# 3_Communication.net
KiCad netlist of a schematic drawn in Altium Designer
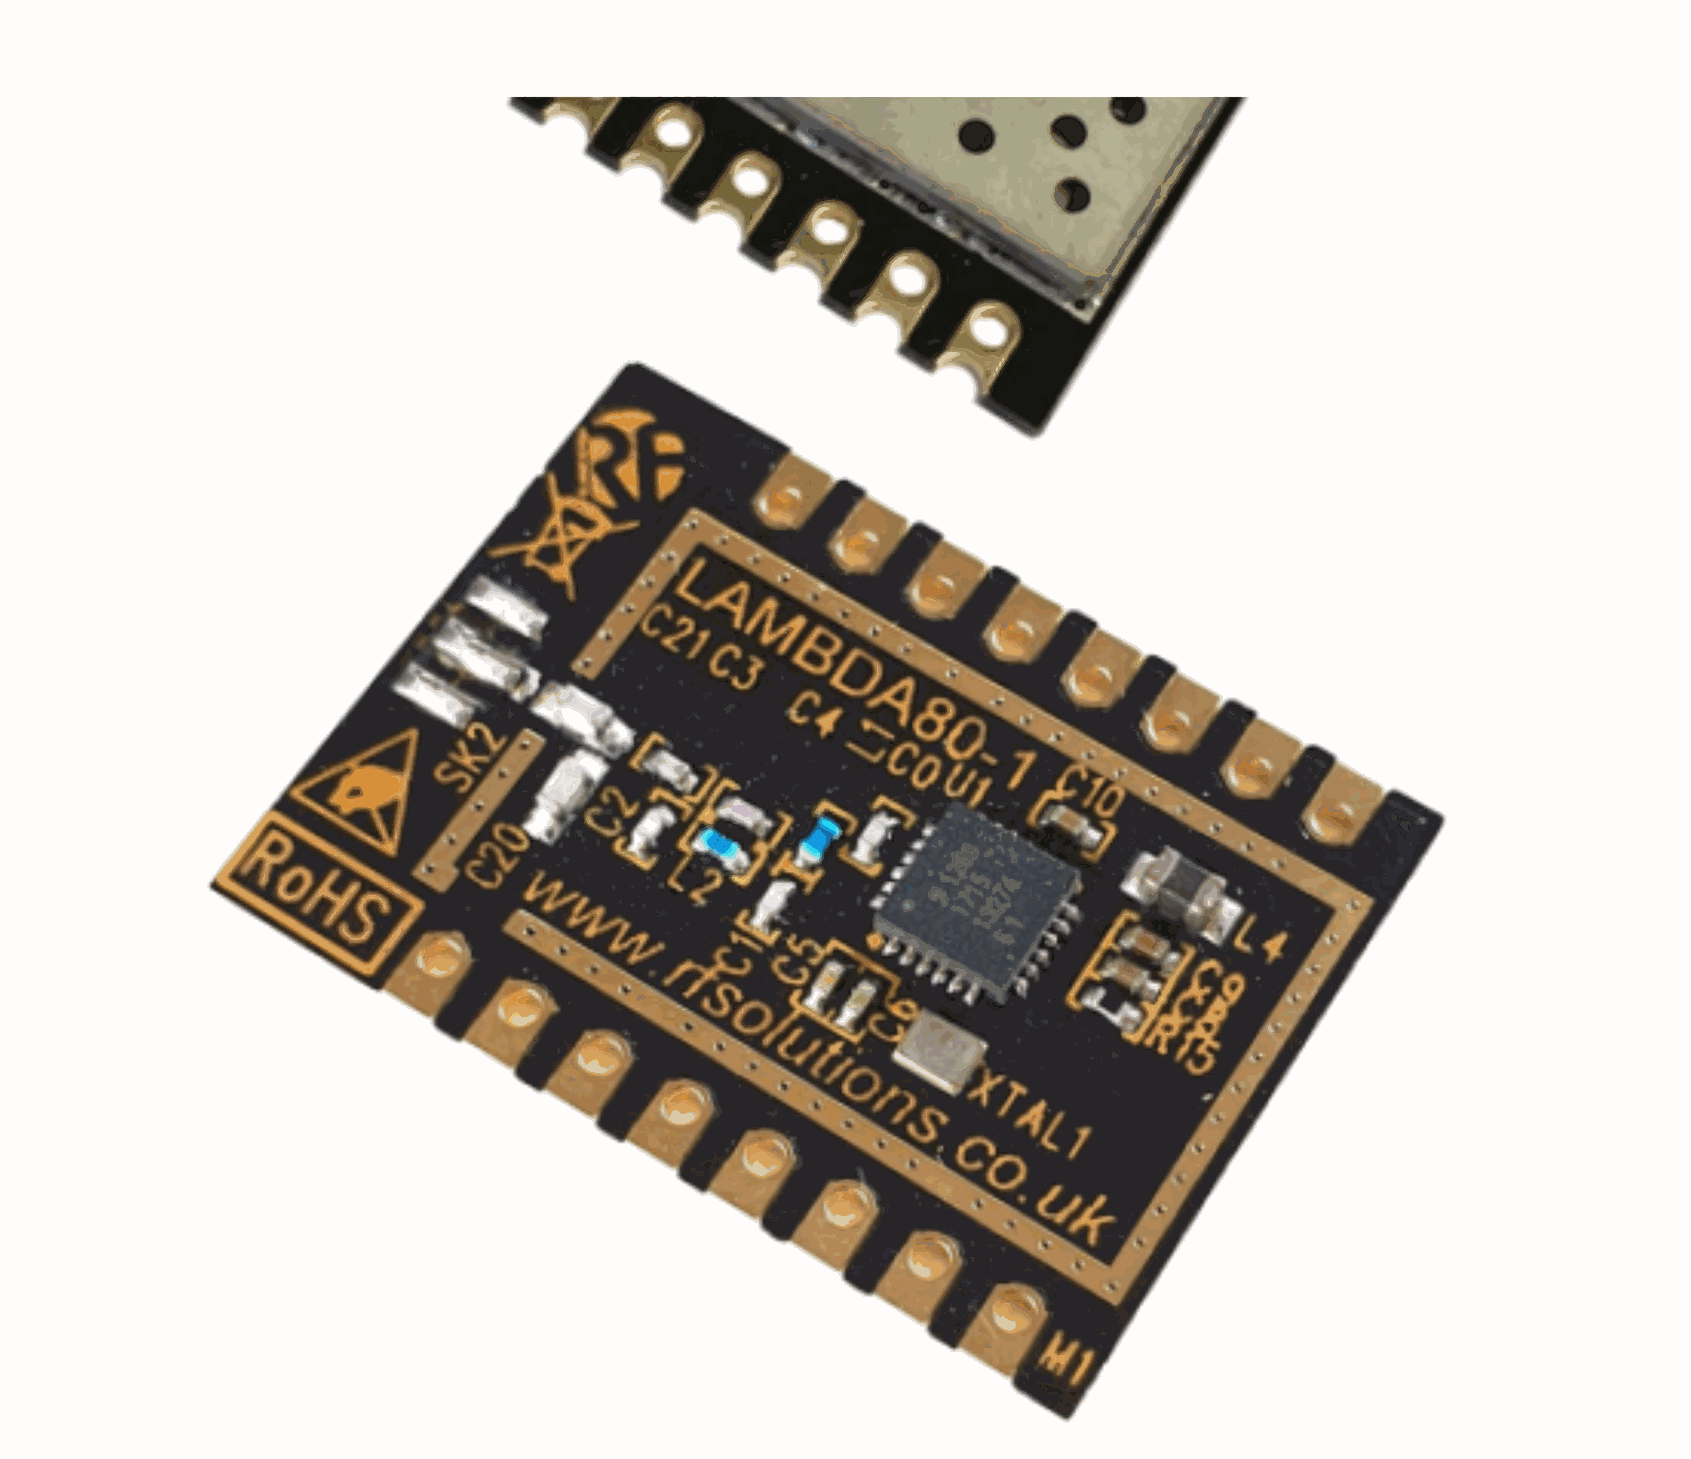
[diagram p0: 3_Communication.SchDoc, top middle]
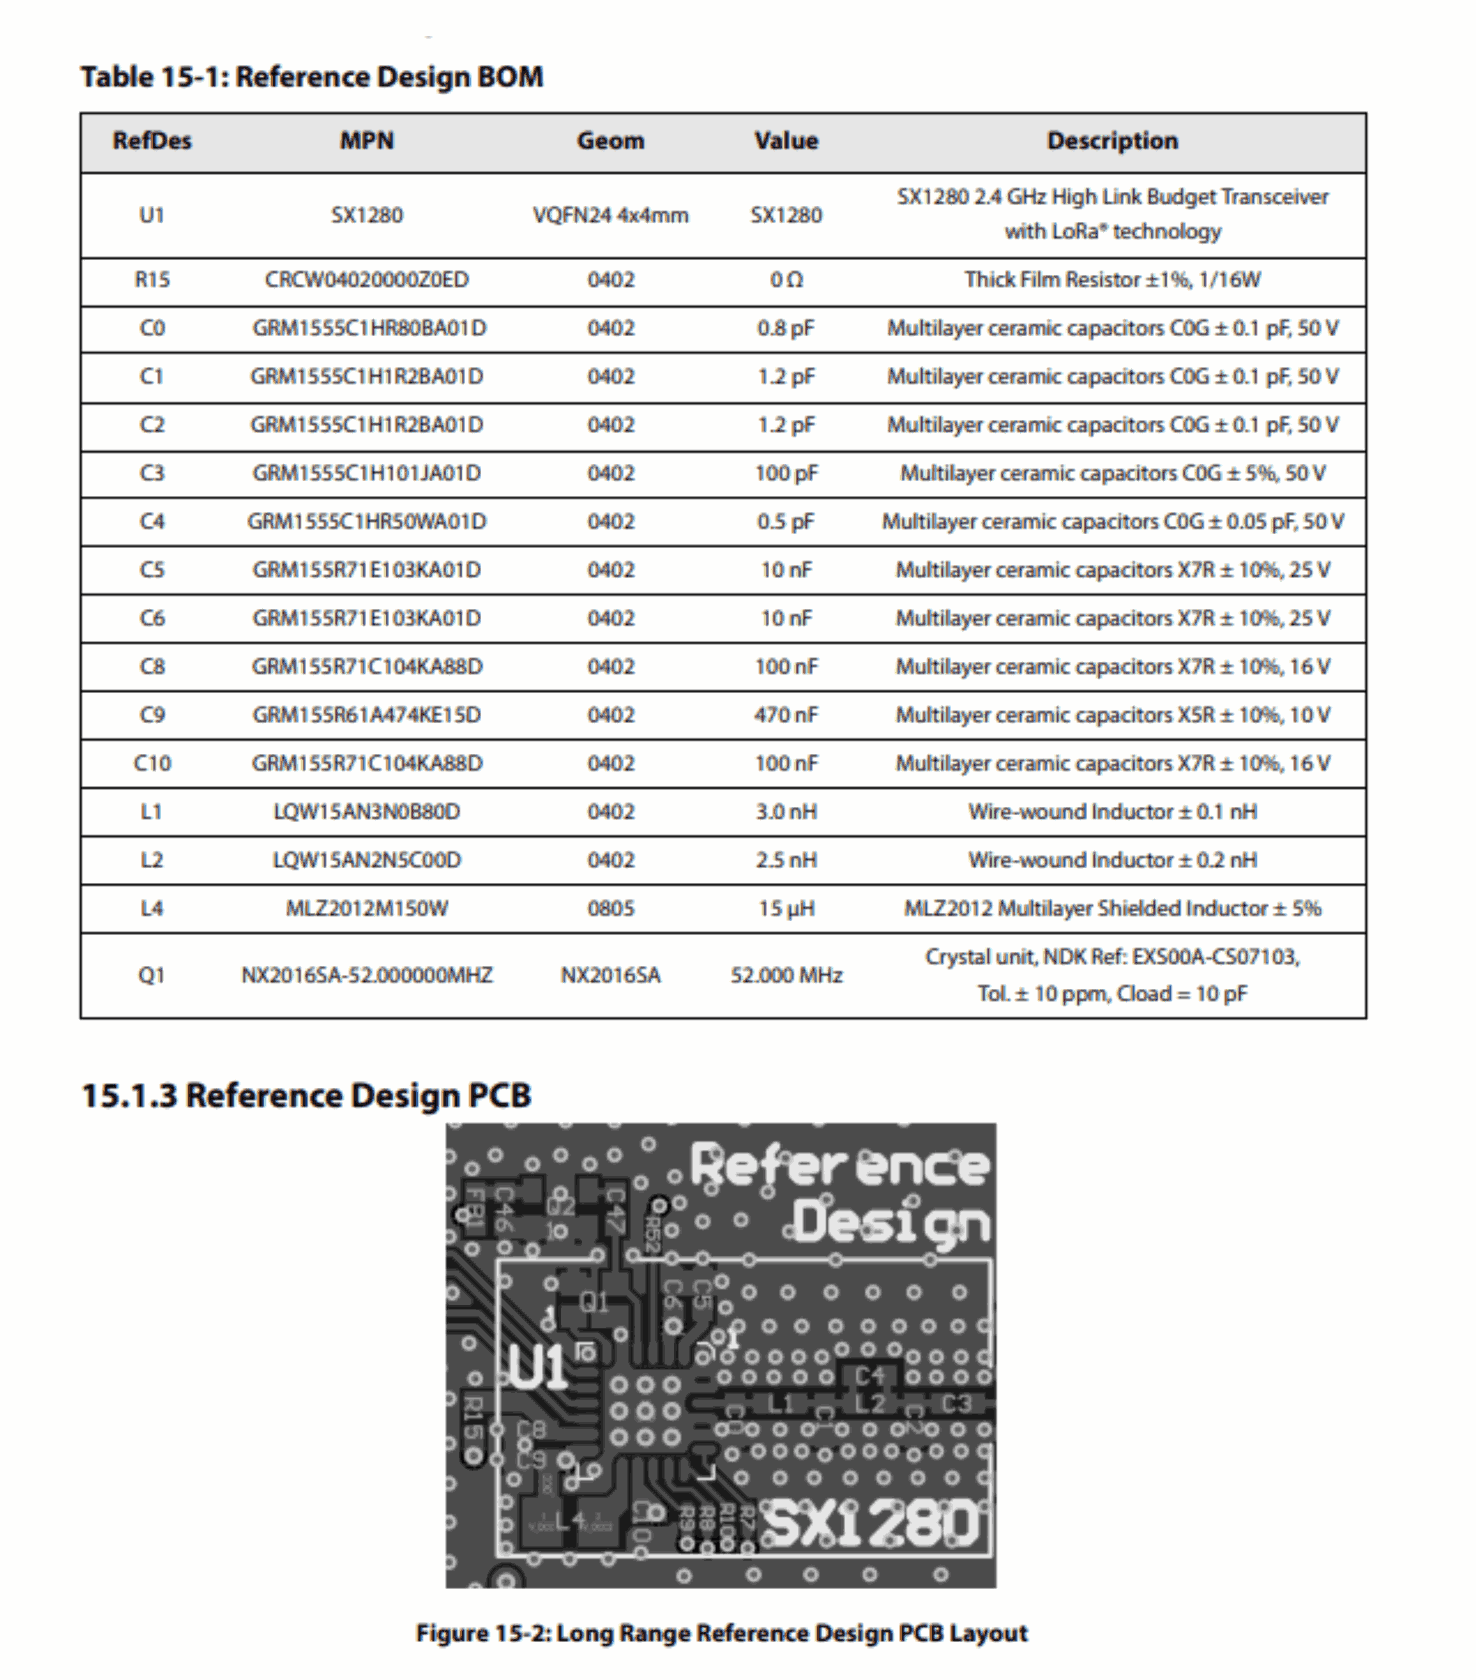
[diagram p1: 3_Communication.SchDoc, top right]
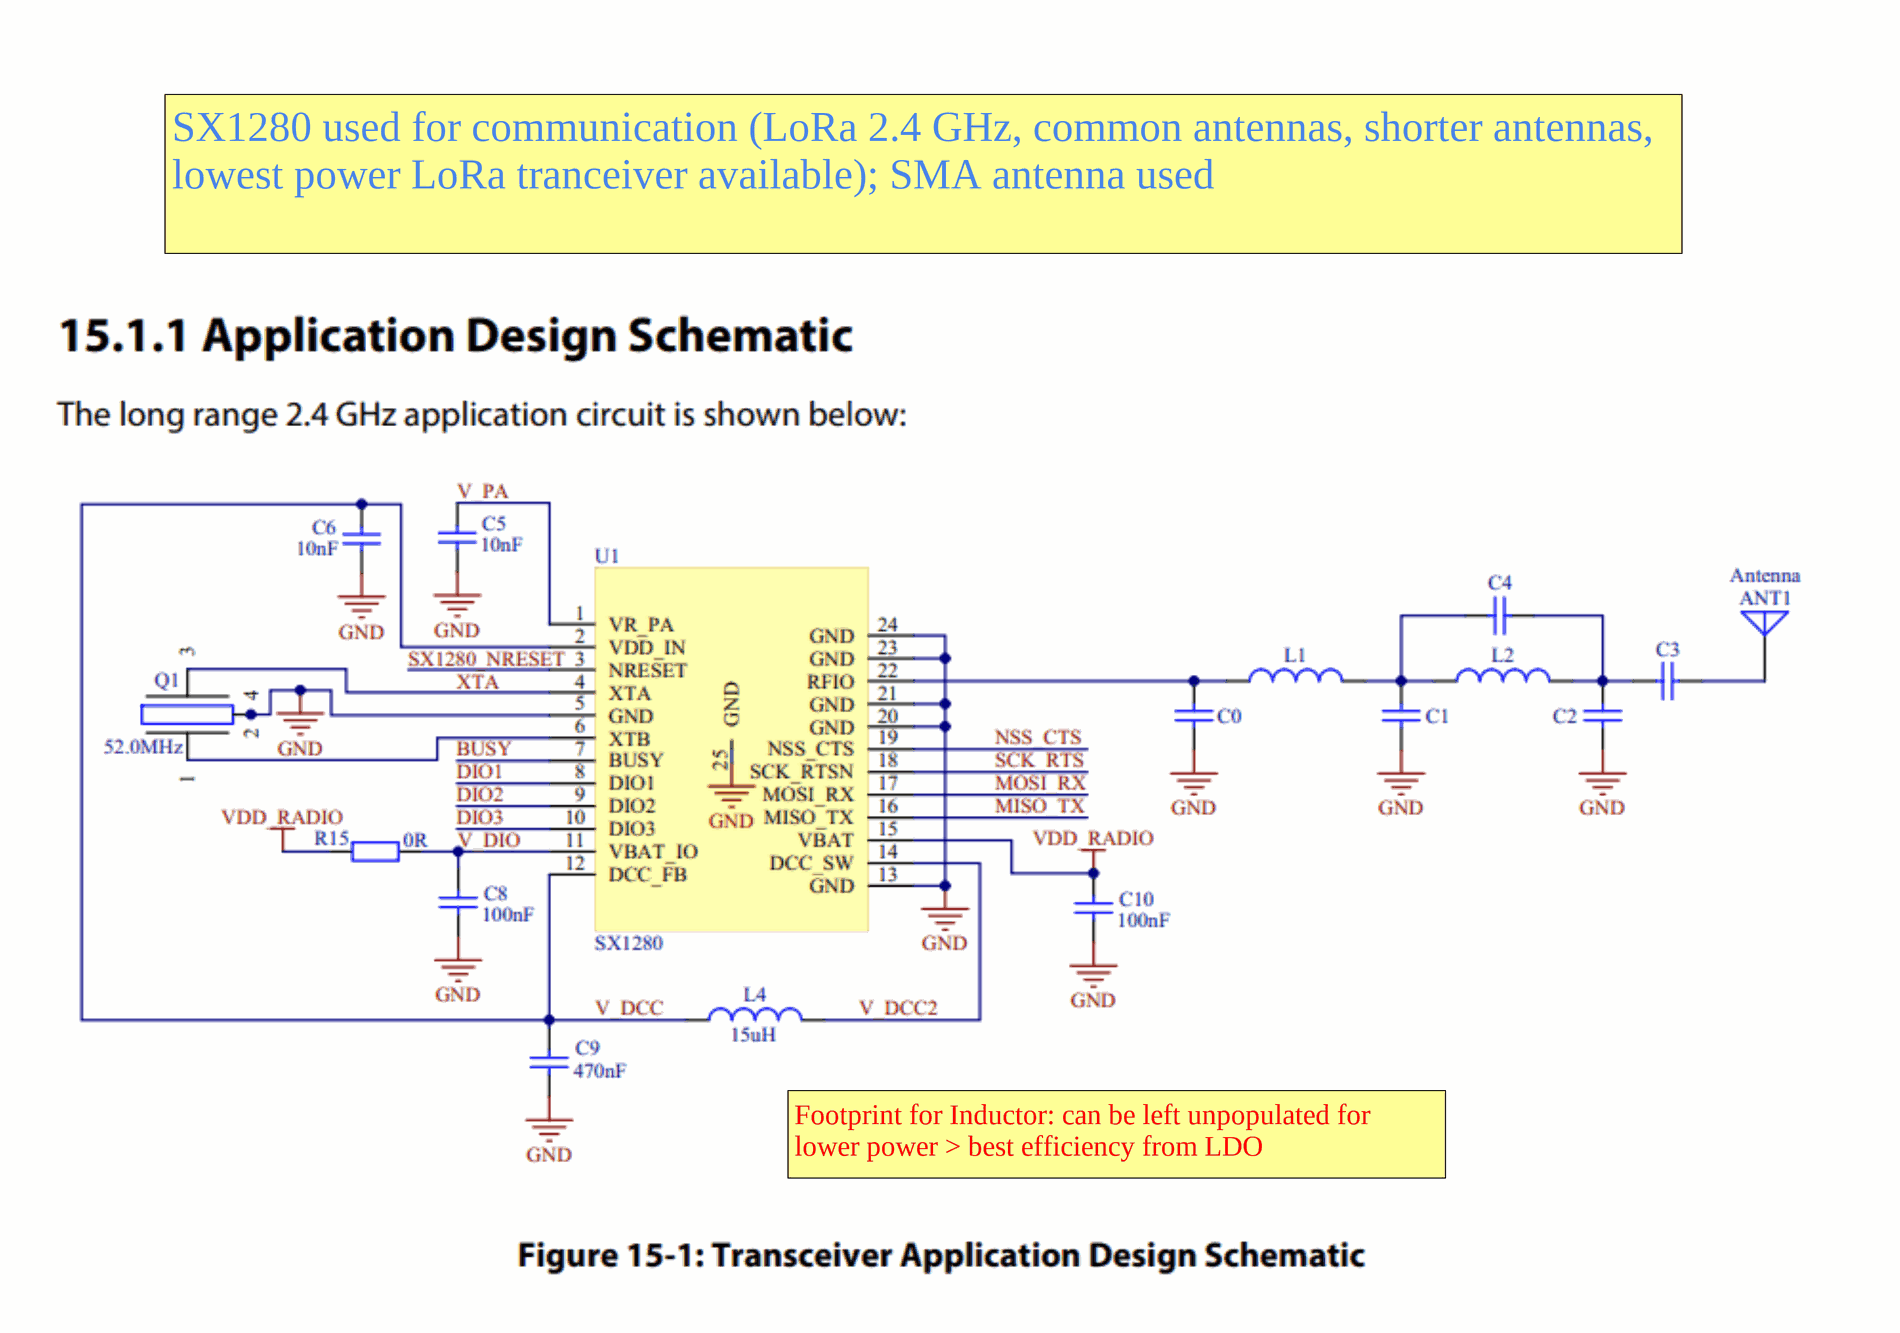
[diagram p2: 3_Communication.SchDoc, bottom left]
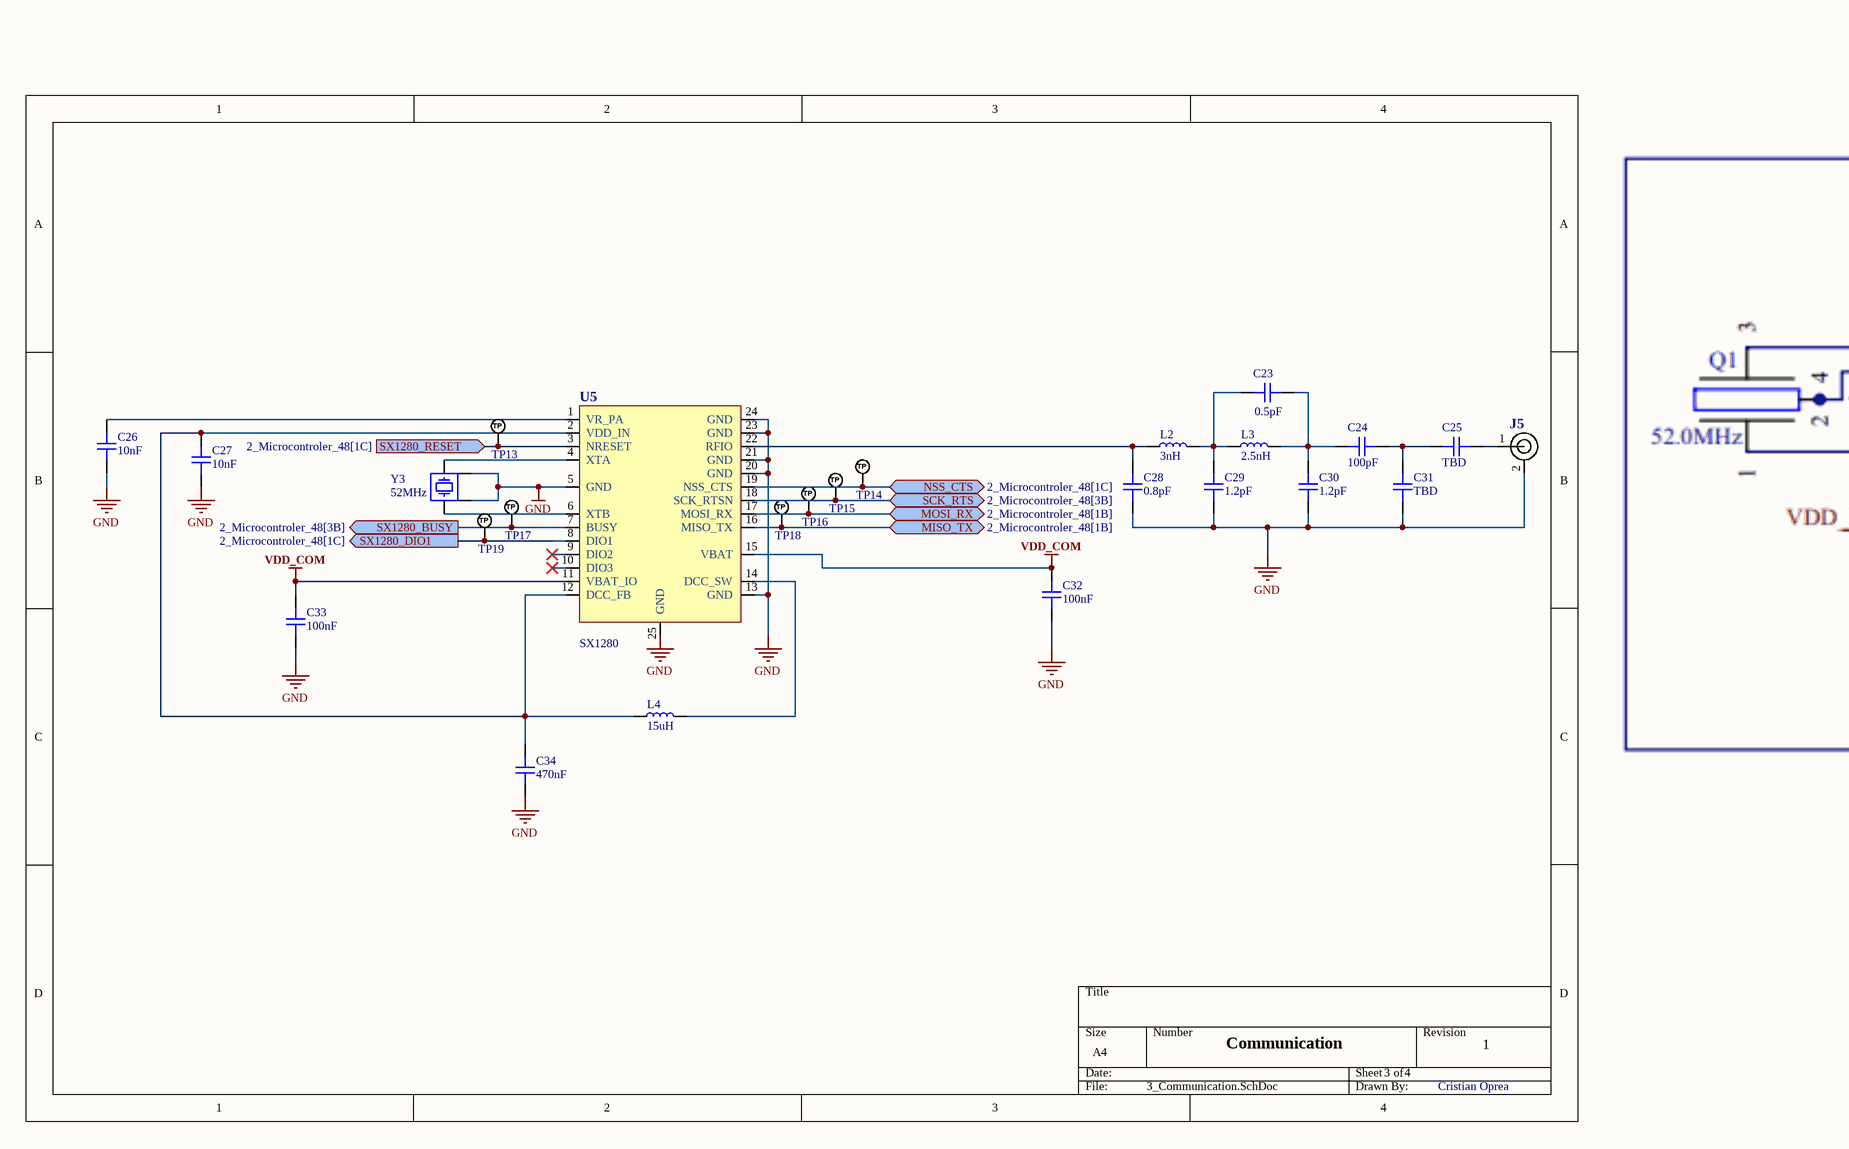
[diagram p3: 3_Communication.SchDoc, bottom middle]
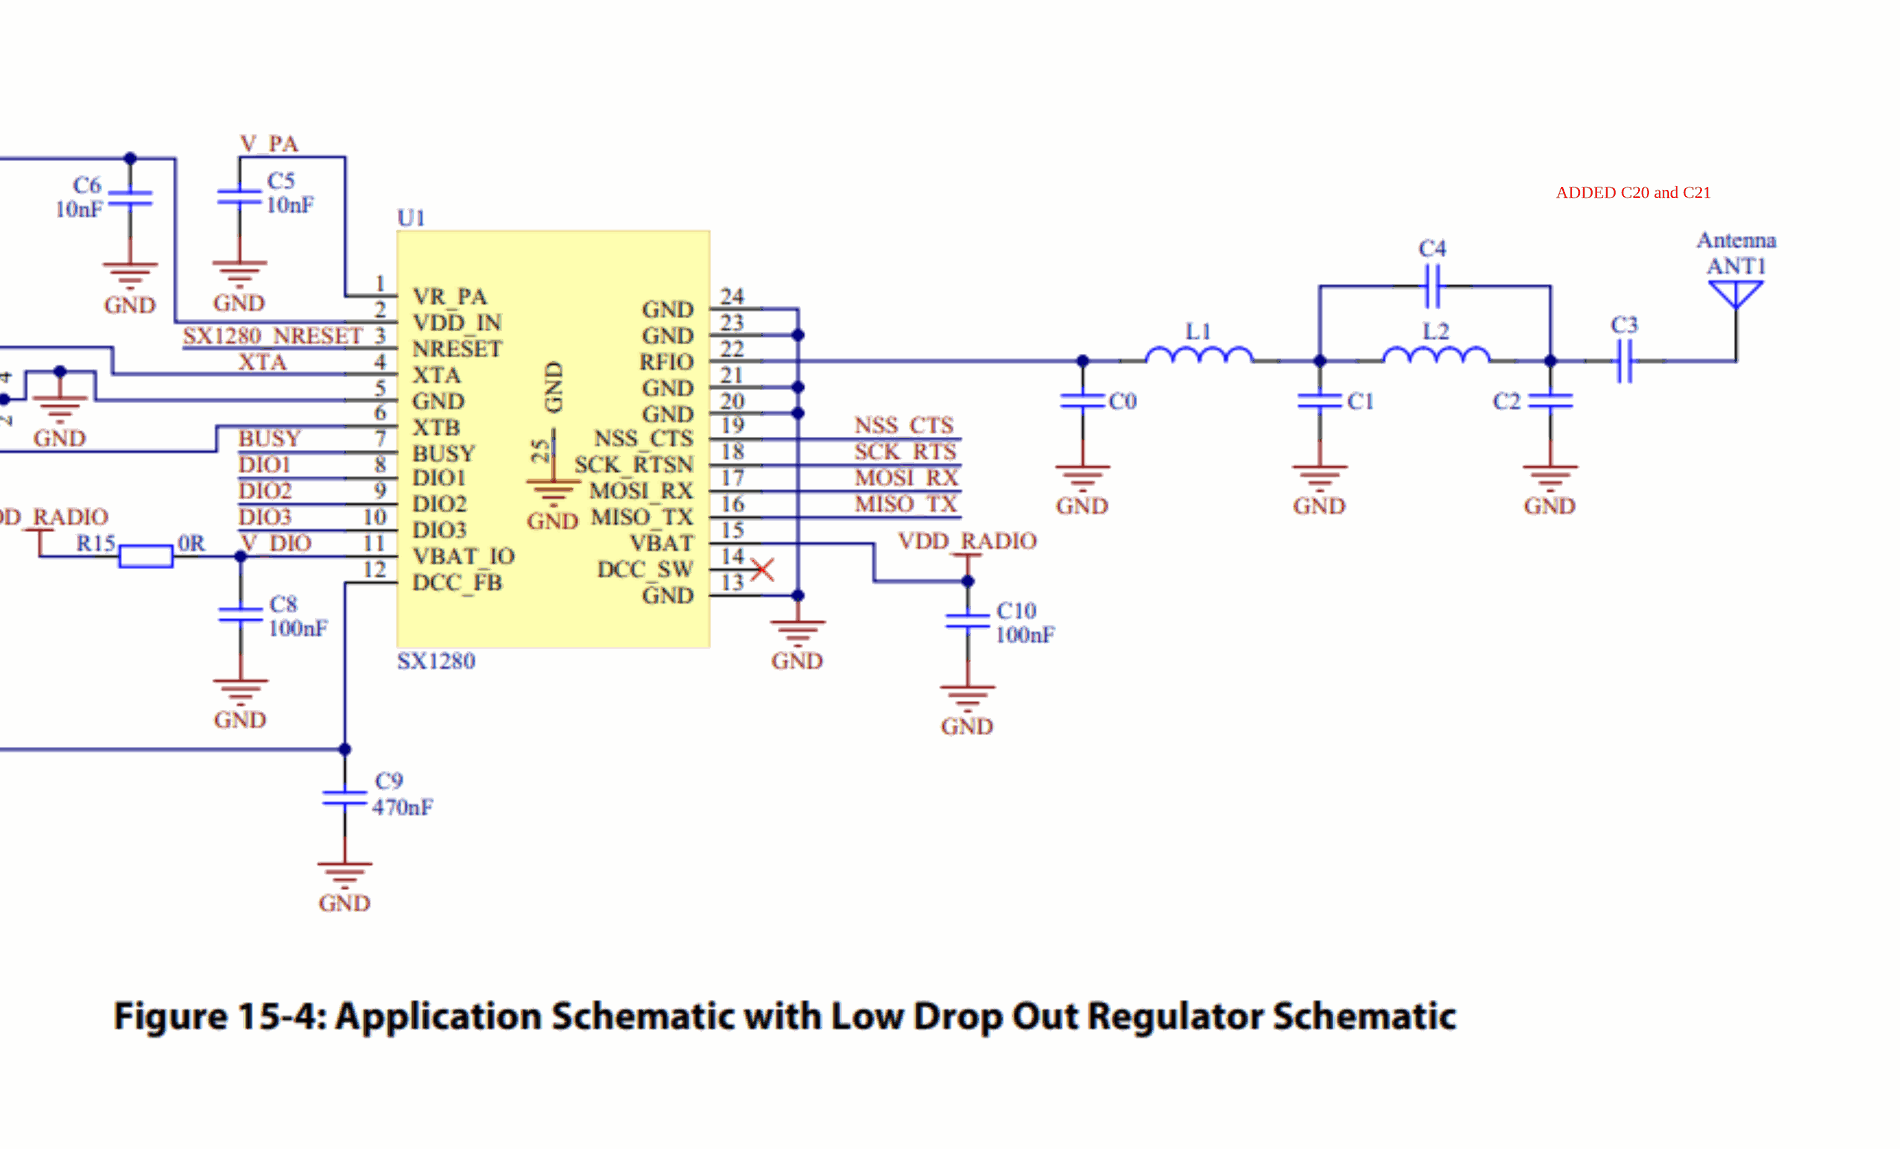
[diagram p4: 3_Communication.SchDoc, bottom right]

(export (version "E")
  (design (tool "Eeschema 10.0.6"))
  (components
    (comp (ref "C23")
      (value "0.5pF")
      (footprint "C0603")
      (description "Capacitor SMD 0603")
      (libsource (lib "Schlib_H2") (part "CAP_0603"))
    )
    (comp (ref "C24")
      (value "100pF")
      (footprint "C0603")
      (description "Capacitor SMD 0603")
      (libsource (lib "Schlib_H2") (part "CAP_0603"))
    )
    (comp (ref "C25")
      (value "TBD")
      (footprint "C0805")
      (description "Capacitor SMD 0805")
      (libsource (lib "Schlib_H2") (part "CAP_0603"))
    )
    (comp (ref "C26")
      (value "10nF")
      (footprint "C0603")
      (description "Capacitor SMD 0603")
      (libsource (lib "Schlib_H2") (part "CAP_0603"))
    )
    (comp (ref "C27")
      (value "10nF")
      (footprint "C0603")
      (description "Capacitor SMD 0603")
      (libsource (lib "Schlib_H2") (part "CAP_0603"))
    )
    (comp (ref "C28")
      (value "0.8pF")
      (footprint "C0603")
      (description "Capacitor SMD 0603")
      (libsource (lib "Schlib_H2") (part "CAP_0603"))
    )
    (comp (ref "C29")
      (value "1.2pF")
      (footprint "C0603")
      (description "Capacitor SMD 0603")
      (libsource (lib "Schlib_H2") (part "CAP_0603"))
    )
    (comp (ref "C30")
      (value "1.2pF")
      (footprint "C0603")
      (description "Capacitor SMD 0603")
      (libsource (lib "Schlib_H2") (part "CAP_0603"))
    )
    (comp (ref "C31")
      (value "TBD")
      (footprint "C0805")
      (description "Capacitor SMD 0805")
      (libsource (lib "Schlib_H2") (part "CAP_0603"))
    )
    (comp (ref "C32")
      (value "100nF")
      (footprint "C0603")
      (description "Capacitor SMD 0603")
      (libsource (lib "Schlib_H2") (part "CAP_0603"))
    )
    (comp (ref "C33")
      (value "100nF")
      (footprint "C0603")
      (description "Capacitor SMD 0603")
      (libsource (lib "Schlib_H2") (part "CAP_0603"))
    )
    (comp (ref "C34")
      (value "470nF")
      (footprint "C0603")
      (description "Capacitor SMD 0603")
      (libsource (lib "Schlib_H2") (part "CAP_0603"))
    )
    (comp (ref "J5")
      (value "SMA_EDGE_CONN")
      (footprint "CON_SMA-EDGE-S")
      (description "RF Connector SMA Female 50 Ohms 18 GHz PCB Edge Mount")
      (fields
        (field (name "MANUFACTURER") "RF Solutions")
        (field (name "MANUFACTURER PART NUMBER") "CON-SMA-EDGE-S")
      )
      (libsource (lib "Schlib_H2") (part "CON-SMA-EDGE-S"))
    )
    (comp (ref "L2")
      (value "3nH")
      (footprint "R0603")
      (description "Inductor SMD 0603")
      (libsource (lib "Schlib_H2") (part "IND_0603"))
    )
    (comp (ref "L3")
      (value "2.5nH")
      (footprint "R0603")
      (description "Inductor SMD 0603")
      (libsource (lib "Schlib_H2") (part "IND_0603"))
    )
    (comp (ref "L4")
      (value "15uH")
      (footprint "IND_3.2_4")
      (description "Inductor SMD 0603")
      (libsource (lib "Schlib_H2") (part "IND_0603"))
    )
    (comp (ref "TP13")
      (value "TP_NOBOM")
      (footprint "TEST_PAD_THD")
      (description "Test Point Round 1mm (NO BOM)")
      (libsource (lib "Schlib_H2") (part "TEST_POINT_RND_1MM"))
    )
    (comp (ref "TP14")
      (value "TP_NOBOM")
      (footprint "TEST_PAD_THD")
      (description "Test Point Round 1mm (NO BOM)")
      (libsource (lib "Schlib_H2") (part "TEST_POINT_RND_1MM"))
    )
    (comp (ref "TP15")
      (value "TP_NOBOM")
      (footprint "TEST_PAD_THD")
      (description "Test Point Round 1mm (NO BOM)")
      (libsource (lib "Schlib_H2") (part "TEST_POINT_RND_1MM"))
    )
    (comp (ref "TP16")
      (value "TP_NOBOM")
      (footprint "TEST_PAD_THD")
      (description "Test Point Round 1mm (NO BOM)")
      (libsource (lib "Schlib_H2") (part "TEST_POINT_RND_1MM"))
    )
    (comp (ref "TP17")
      (value "TP_NOBOM")
      (footprint "TEST_PAD_THD")
      (description "Test Point Round 1mm (NO BOM)")
      (libsource (lib "Schlib_H2") (part "TEST_POINT_RND_1MM"))
    )
    (comp (ref "TP18")
      (value "TP_NOBOM")
      (footprint "TEST_PAD_THD")
      (description "Test Point Round 1mm (NO BOM)")
      (libsource (lib "Schlib_H2") (part "TEST_POINT_RND_1MM"))
    )
    (comp (ref "TP19")
      (value "TP_NOBOM")
      (footprint "TEST_PAD_THD")
      (description "Test Point Round 1mm (NO BOM)")
      (libsource (lib "Schlib_H2") (part "TEST_POINT_RND_1MM"))
    )
    (comp (ref "U5")
      (value "SX1280")
      (footprint "QFN-24_4x4_0.5")
      (description "Low power LoRa transceiver operating at 2.4GHz with ranging capability")
      (libsource (lib "Schlib_H2") (part "SX1280"))
    )
    (comp (ref "Y3")
      (value "52MHz")
      (footprint "CRYSTAL_2016_4P")
      (description "Crystal")
      (fields
        (field (name "MANUFACTURER") "Epson")
        (field (name "MANUFACTURER PART NUMBER") "TSX-3225 24.0000MF15X-AC")
      )
      (libsource (lib "Schlib_H2") (part "Crystal"))
    )
  )
  (nets
    (net (code "1") (name "/MISO_TX") (class "Default")
      (node (ref "TP18") (pin "1") (pinfunction "TP_1") (pintype "passive"))
      (node (ref "U5") (pin "16") (pinfunction "MISO_TX_16") (pintype "passive"))
    )
    (net (code "2") (name "/MOSI_RX") (class "Default")
      (node (ref "TP16") (pin "1") (pinfunction "TP_1") (pintype "passive"))
      (node (ref "U5") (pin "17") (pinfunction "MOSI_RX_17") (pintype "passive"))
    )
    (net (code "3") (name "/NSS_CTS") (class "Default")
      (node (ref "TP14") (pin "1") (pinfunction "TP_1") (pintype "passive"))
      (node (ref "U5") (pin "19") (pinfunction "NSS_CTS_19") (pintype "passive"))
    )
    (net (code "4") (name "/SCK_RTS") (class "Default")
      (node (ref "TP15") (pin "1") (pinfunction "TP_1") (pintype "passive"))
      (node (ref "U5") (pin "18") (pinfunction "SCK_RTSN_18") (pintype "passive"))
    )
    (net (code "5") (name "/SX1280_BUSY") (class "Default")
      (node (ref "TP17") (pin "1") (pinfunction "TP_1") (pintype "passive"))
      (node (ref "U5") (pin "7") (pinfunction "BUSY_7") (pintype "passive"))
    )
    (net (code "6") (name "/SX1280_DIO1") (class "Default")
      (node (ref "TP19") (pin "1") (pinfunction "TP_1") (pintype "passive"))
      (node (ref "U5") (pin "8") (pinfunction "DIO1_8") (pintype "passive"))
    )
    (net (code "7") (name "/SX1280_RESET") (class "Default")
      (node (ref "TP13") (pin "1") (pinfunction "TP_1") (pintype "passive"))
      (node (ref "U5") (pin "3") (pinfunction "NRESET_3") (pintype "passive"))
    )
    (net (code "8") (name "GND") (class "Default")
      (node (ref "C26") (pin "1") (pinfunction "1_1") (pintype "passive"))
      (node (ref "C27") (pin "1") (pinfunction "1_1") (pintype "passive"))
      (node (ref "C28") (pin "1") (pinfunction "1_1") (pintype "passive"))
      (node (ref "C29") (pin "1") (pinfunction "1_1") (pintype "passive"))
      (node (ref "C30") (pin "1") (pinfunction "1_1") (pintype "passive"))
      (node (ref "C31") (pin "1") (pinfunction "1_1") (pintype "passive"))
      (node (ref "C32") (pin "1") (pinfunction "1_1") (pintype "passive"))
      (node (ref "C33") (pin "1") (pinfunction "1_1") (pintype "passive"))
      (node (ref "C34") (pin "1") (pinfunction "1_1") (pintype "passive"))
      (node (ref "J5") (pin "2") (pinfunction "2_2") (pintype "passive"))
      (node (ref "U5") (pin "13") (pinfunction "GND_13") (pintype "passive"))
      (node (ref "U5") (pin "20") (pinfunction "GND_20") (pintype "passive"))
      (node (ref "U5") (pin "21") (pinfunction "GND_21") (pintype "passive"))
      (node (ref "U5") (pin "23") (pinfunction "GND_23") (pintype "passive"))
      (node (ref "U5") (pin "24") (pinfunction "GND_24") (pintype "passive"))
      (node (ref "U5") (pin "25") (pinfunction "GND_25") (pintype "passive"))
      (node (ref "U5") (pin "5") (pinfunction "GND_5") (pintype "passive"))
      (node (ref "Y3") (pin "2") (pinfunction "2_2") (pintype "passive"))
      (node (ref "Y3") (pin "4") (pinfunction "4_4") (pintype "passive"))
    )
    (net (code "9") (name "Net-(C23-Pad1)") (class "Default")
      (node (ref "C23") (pin "1") (pinfunction "1_1") (pintype "passive"))
      (node (ref "C24") (pin "2") (pinfunction "2_2") (pintype "passive"))
      (node (ref "C30") (pin "2") (pinfunction "2_2") (pintype "passive"))
      (node (ref "L3") (pin "2") (pinfunction "2_2") (pintype "passive"))
    )
    (net (code "10") (name "Net-(C23-Pad2)") (class "Default")
      (node (ref "C23") (pin "2") (pinfunction "2_2") (pintype "passive"))
      (node (ref "C29") (pin "2") (pinfunction "2_2") (pintype "passive"))
      (node (ref "L2") (pin "2") (pinfunction "2_2") (pintype "passive"))
      (node (ref "L3") (pin "1") (pinfunction "1_1") (pintype "passive"))
    )
    (net (code "11") (name "Net-(C24-Pad1)") (class "Default")
      (node (ref "C24") (pin "1") (pinfunction "1_1") (pintype "passive"))
      (node (ref "C25") (pin "2") (pinfunction "2_2") (pintype "passive"))
      (node (ref "C31") (pin "2") (pinfunction "2_2") (pintype "passive"))
    )
    (net (code "12") (name "Net-(C25-Pad1)") (class "Default")
      (node (ref "C25") (pin "1") (pinfunction "1_1") (pintype "passive"))
      (node (ref "J5") (pin "1") (pinfunction "1_1") (pintype "passive"))
    )
    (net (code "13") (name "Net-(U5-DCC_FB)") (class "Default")
      (node (ref "C27") (pin "2") (pinfunction "2_2") (pintype "passive"))
      (node (ref "C34") (pin "2") (pinfunction "2_2") (pintype "passive"))
      (node (ref "L4") (pin "1") (pinfunction "1_1") (pintype "passive"))
      (node (ref "U5") (pin "12") (pinfunction "DCC_FB_12") (pintype "passive"))
      (node (ref "U5") (pin "2") (pinfunction "VDD_IN_2") (pintype "passive"))
    )
    (net (code "14") (name "Net-(U5-DCC_SW)") (class "Default")
      (node (ref "L4") (pin "2") (pinfunction "2_2") (pintype "passive"))
      (node (ref "U5") (pin "14") (pinfunction "DCC_SW_14") (pintype "passive"))
    )
    (net (code "15") (name "Net-(U5-RFIO)") (class "Default")
      (node (ref "C28") (pin "2") (pinfunction "2_2") (pintype "passive"))
      (node (ref "L2") (pin "1") (pinfunction "1_1") (pintype "passive"))
      (node (ref "U5") (pin "22") (pinfunction "RFIO_22") (pintype "passive"))
    )
    (net (code "16") (name "Net-(U5-VR_PA)") (class "Default")
      (node (ref "C26") (pin "2") (pinfunction "2_2") (pintype "passive"))
      (node (ref "U5") (pin "1") (pinfunction "VR_PA_1") (pintype "passive"))
    )
    (net (code "17") (name "Net-(U5-XTA)") (class "Default")
      (node (ref "U5") (pin "4") (pinfunction "XTA_4") (pintype "passive"))
      (node (ref "Y3") (pin "3") (pinfunction "3_3") (pintype "passive"))
    )
    (net (code "18") (name "Net-(U5-XTB)") (class "Default")
      (node (ref "U5") (pin "6") (pinfunction "XTB_6") (pintype "passive"))
      (node (ref "Y3") (pin "1") (pinfunction "1_1") (pintype "passive"))
    )
    (net (code "19") (name "VDD_COM") (class "Default")
      (node (ref "C32") (pin "2") (pinfunction "2_2") (pintype "passive"))
      (node (ref "C33") (pin "2") (pinfunction "2_2") (pintype "passive"))
      (node (ref "U5") (pin "11") (pinfunction "VBAT_IO_11") (pintype "passive"))
      (node (ref "U5") (pin "15") (pinfunction "VBAT_15") (pintype "passive"))
    )
    (net (code "20") (name "unconnected-(U5-DIO2-Pad9)") (class "Default")
      (node (ref "U5") (pin "9") (pinfunction "DIO2_9") (pintype "passive+no_connect"))
    )
    (net (code "21") (name "unconnected-(U5-DIO3-Pad10)") (class "Default")
      (node (ref "U5") (pin "10") (pinfunction "DIO3_10") (pintype "passive+no_connect"))
    )
  )
)
